# thru-cal-board.net
KiCad netlist of a schematic drawn in Altium Designer
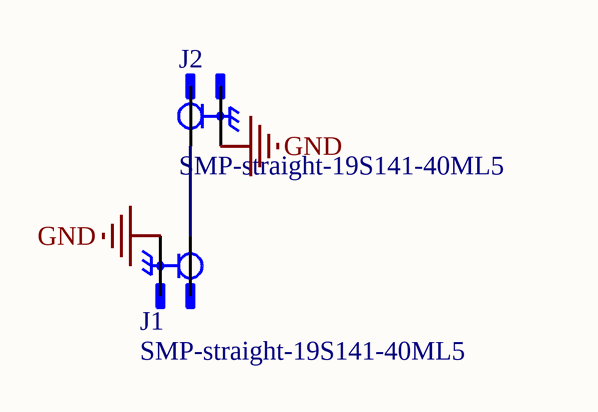
[diagram p0: thru-cal-board.SchDoc]

(export (version "E")
  (design (tool "Eeschema 10.0.6"))
  (components
    (comp (ref "J1")
      (value "SMP-straight-19S141-40ML5")
      (footprint "rosenberger-19S141-40ML5")
      (description "SMP Connector Plug, Male Pin 50Ohm Surface Mount Solder")
      (fields (field (name "MP") "853050232") (field (name "MF") "Molex"))
      (libsource (lib "") (part "SMP-straight-19S141-40ML5_1"))
    )
    (comp (ref "J2")
      (value "SMP-straight-19S141-40ML5")
      (footprint "rosenberger-19S141-40ML5")
      (description "SMP Connector Plug, Male Pin 50Ohm Surface Mount Solder")
      (fields (field (name "MP") "853050232") (field (name "MF") "Molex"))
      (libsource (lib "SchlibLafe") (part "SMP-straight-19S141-40ML5"))
    )
  )
  (nets
    (net (code "1") (name "GND") (class "Default")
      (node (ref "J1") (pin "gnd") (pinfunction "gnd_gnd") (pintype "passive"))
      (node (ref "J2") (pin "gnd") (pinfunction "gnd_gnd") (pintype "passive"))
    )
    (net (code "2") (name "Net-(J1-Pad1)") (class "Default")
      (node (ref "J1") (pin "1") (pinfunction "1_1") (pintype "passive"))
      (node (ref "J2") (pin "1") (pinfunction "1_1") (pintype "passive"))
    )
  )
)
